# mano_rev_1_1.net
KiCad netlist of a schematic drawn in EAGLE
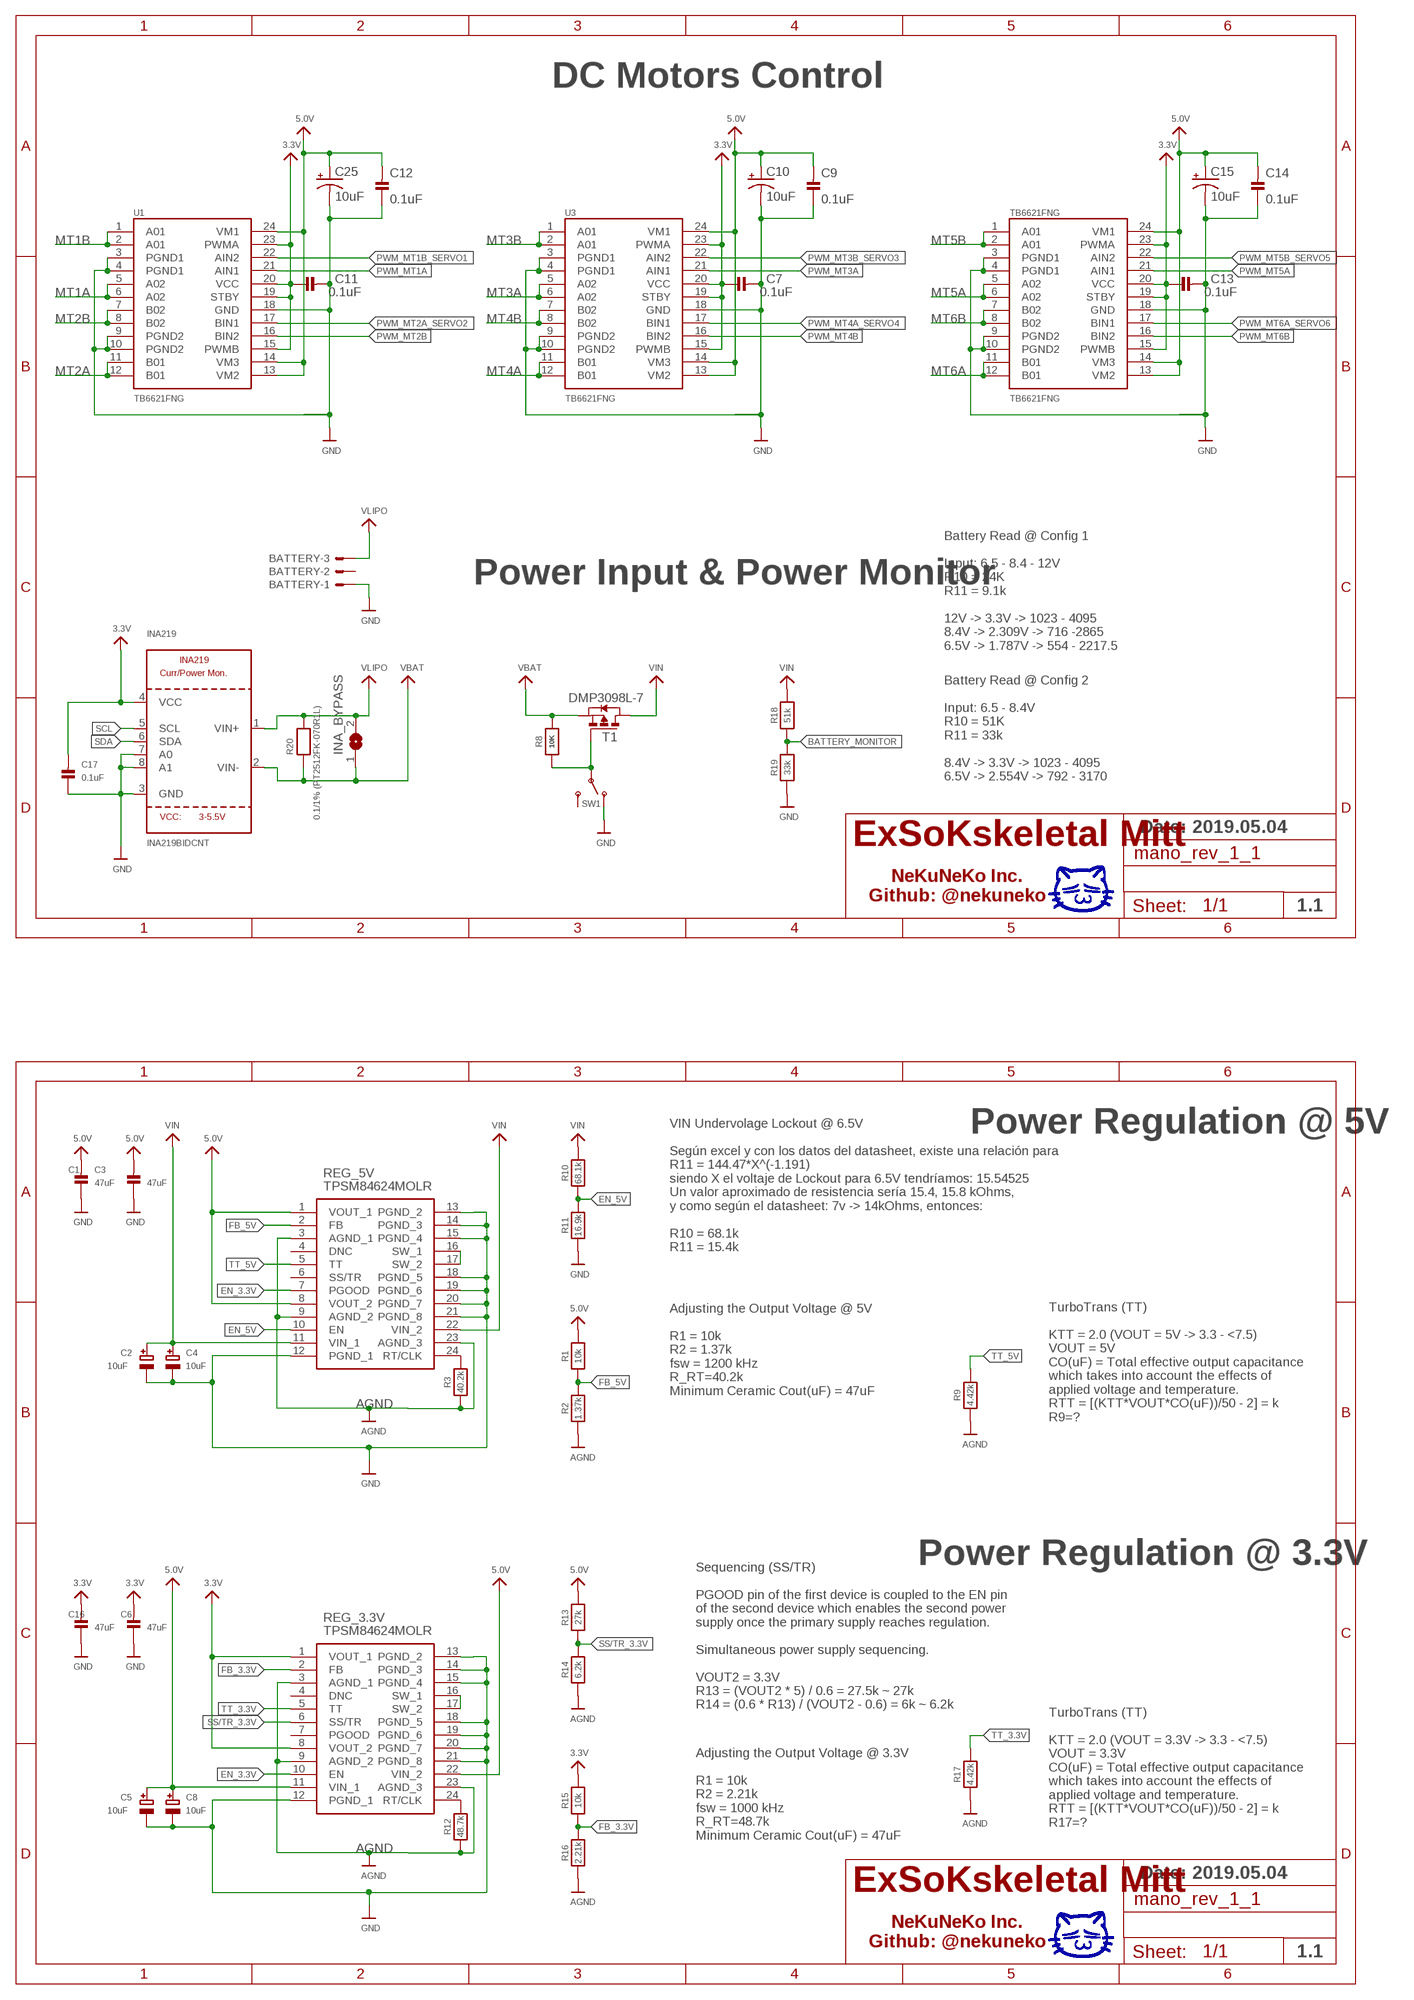
[diagram p0: schematic, sheet 1, part 1 of 2]
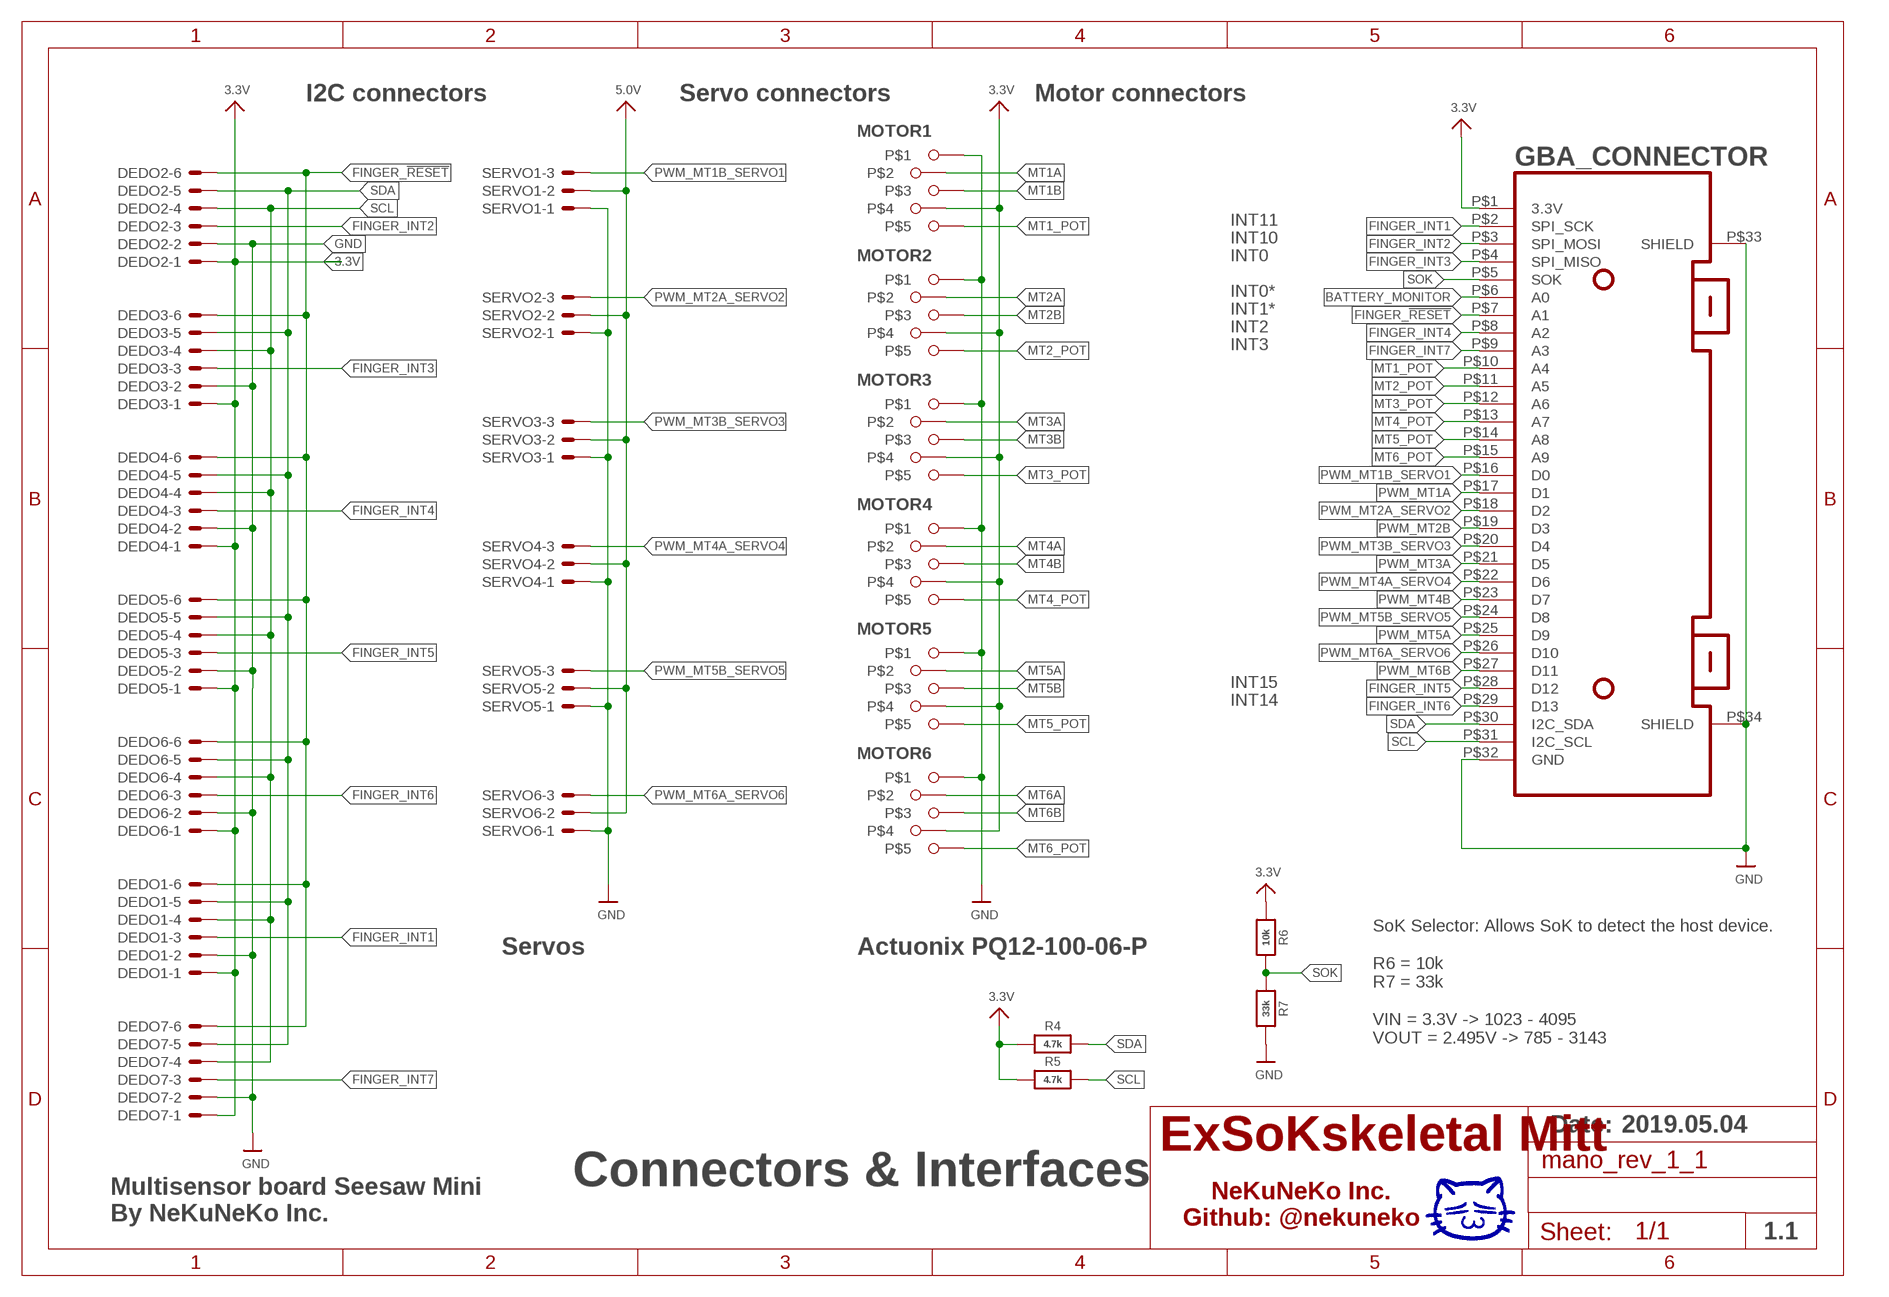
[diagram p1: schematic, sheet 1, part 2 of 2]

(export (version "E")
  (design (tool "Eeschema 10.0.6"))
  (components
    (comp (ref "BATTERY")
      (value "JST-XH-03-PIN-LONG-PAD")
      (footprint "eagle-import:JST-XH-03-PACKAGE-LONG-PAD")
      (libsource (lib "eagle-import") (part "JST-XH-03-PIN-LONG-PAD"))
    )
    (comp (ref "C1")
      (value "47uF")
      (footprint "eagle-import:_0603")
      (libsource (lib "eagle-import") (part "CAP_CERAMIC_0603"))
    )
    (comp (ref "C2")
      (value "10uF")
      (footprint "eagle-import:EIA3216-18_A-R")
      (libsource (lib "eagle-import") (part "CAP_TANTALUMA/3216_REFLOW"))
    )
    (comp (ref "C3")
      (value "47uF")
      (footprint "eagle-import:_0603")
      (libsource (lib "eagle-import") (part "CAP_CERAMIC_0603"))
    )
    (comp (ref "C4")
      (value "10uF")
      (footprint "eagle-import:EIA3216-18_A-R")
      (libsource (lib "eagle-import") (part "CAP_TANTALUMA/3216_REFLOW"))
    )
    (comp (ref "C5")
      (value "10uF")
      (footprint "eagle-import:EIA3216-18_A-R")
      (libsource (lib "eagle-import") (part "CAP_TANTALUMA/3216_REFLOW"))
    )
    (comp (ref "C6")
      (value "47uF")
      (footprint "eagle-import:_0603")
      (libsource (lib "eagle-import") (part "CAP_CERAMIC_0603"))
    )
    (comp (ref "C7")
      (value "0.1uF")
      (footprint "eagle-import:_0603")
      (libsource (lib "eagle-import") (part "CAP_CERAMIC_0603"))
    )
    (comp (ref "C8")
      (value "10uF")
      (footprint "eagle-import:EIA3216-18_A-R")
      (libsource (lib "eagle-import") (part "CAP_TANTALUMA/3216_REFLOW"))
    )
    (comp (ref "C9")
      (value "0.1uF")
      (footprint "eagle-import:_0603")
      (libsource (lib "eagle-import") (part "CAP_CERAMIC_0603"))
    )
    (comp (ref "C10")
      (value "10uF")
      (footprint "eagle-import:0603-POLAR")
      (fields (field (name "MPN") "F981A106MMA"))
      (libsource (lib "eagle-import") (part "10UF-POLAR-0603-6.3V-20%(TANT)"))
    )
    (comp (ref "C11")
      (value "0.1uF")
      (footprint "eagle-import:_0603")
      (libsource (lib "eagle-import") (part "CAP_CERAMIC_0603"))
    )
    (comp (ref "C12")
      (value "0.1uF")
      (footprint "eagle-import:_0603")
      (libsource (lib "eagle-import") (part "CAP_CERAMIC_0603"))
    )
    (comp (ref "C13")
      (value "0.1uF")
      (footprint "eagle-import:_0603")
      (libsource (lib "eagle-import") (part "CAP_CERAMIC_0603"))
    )
    (comp (ref "C14")
      (value "0.1uF")
      (footprint "eagle-import:_0603")
      (libsource (lib "eagle-import") (part "CAP_CERAMIC_0603"))
    )
    (comp (ref "C15")
      (value "10uF")
      (footprint "eagle-import:0603-POLAR")
      (fields (field (name "MPN") "F981A106MMA"))
      (libsource (lib "eagle-import") (part "10UF-POLAR-0603-6.3V-20%(TANT)"))
    )
    (comp (ref "C16")
      (value "47uF")
      (footprint "eagle-import:_0603")
      (libsource (lib "eagle-import") (part "CAP_CERAMIC_0603"))
    )
    (comp (ref "C17")
      (value "0.1uF")
      (footprint "eagle-import:_0603")
      (libsource (lib "eagle-import") (part "CAP_CERAMIC_0603"))
    )
    (comp (ref "C25")
      (value "10uF")
      (footprint "eagle-import:0603-POLAR")
      (fields (field (name "MPN") "F981A106MMA"))
      (libsource (lib "eagle-import") (part "10UF-POLAR-0603-6.3V-20%(TANT)"))
    )
    (comp (ref "DEDO1")
      (value "FINGER_1")
      (footprint "eagle-import:BM06B-SRSS-TB")
      (libsource (lib "eagle-import") (part "?M06B-SRSS-TBB"))
    )
    (comp (ref "DEDO2")
      (value "FINGER_2")
      (footprint "eagle-import:BM06B-SRSS-TB")
      (libsource (lib "eagle-import") (part "?M06B-SRSS-TBB"))
    )
    (comp (ref "DEDO3")
      (value "FINGER_3")
      (footprint "eagle-import:BM06B-SRSS-TB")
      (libsource (lib "eagle-import") (part "?M06B-SRSS-TBB"))
    )
    (comp (ref "DEDO4")
      (value "FINGER_4")
      (footprint "eagle-import:BM06B-SRSS-TB")
      (libsource (lib "eagle-import") (part "?M06B-SRSS-TBB"))
    )
    (comp (ref "DEDO5")
      (value "FINGER_5")
      (footprint "eagle-import:BM06B-SRSS-TB")
      (libsource (lib "eagle-import") (part "?M06B-SRSS-TBB"))
    )
    (comp (ref "DEDO6")
      (value "FINGER_6")
      (footprint "eagle-import:BM06B-SRSS-TB")
      (libsource (lib "eagle-import") (part "?M06B-SRSS-TBB"))
    )
    (comp (ref "DEDO7")
      (value "FINGER_7")
      (footprint "eagle-import:BM06B-SRSS-TB")
      (libsource (lib "eagle-import") (part "?M06B-SRSS-TBB"))
    )
    (comp (ref "GBA_CONNECTOR")
      (value "GBA_CARTRIDGE")
      (footprint "eagle-import:GBA_CARTRIDGE")
      (libsource (lib "eagle-import") (part "GBA_CARTRIDGE"))
    )
    (comp (ref "INA219")
      (value "INA219BIDCNT")
      (footprint "eagle-import:SOT23-8")
      (libsource (lib "eagle-import") (part "INA219"))
    )
    (comp (ref "INA_BYPASS")
      (value "SOLDERJUMPERREFLOW_NOPASTE")
      (footprint "eagle-import:SOLDERJUMPER_REFLOW_NOPASTE")
      (libsource (lib "eagle-import") (part "SOLDERJUMPERREFLOW_NOPASTE"))
    )
    (comp (ref "MOTOR1")
      (value "Actuonix PQ12-100-06-P")
      (footprint "eagle-import:5PIN")
      (libsource (lib "eagle-import") (part "5PIN"))
    )
    (comp (ref "MOTOR2")
      (value "Actuonix PQ12-100-06-P")
      (footprint "eagle-import:5PIN")
      (libsource (lib "eagle-import") (part "5PIN"))
    )
    (comp (ref "MOTOR3")
      (value "Actuonix PQ12-100-06-P")
      (footprint "eagle-import:5PIN")
      (libsource (lib "eagle-import") (part "5PIN"))
    )
    (comp (ref "MOTOR4")
      (value "Actuonix PQ12-100-06-P")
      (footprint "eagle-import:5PIN")
      (libsource (lib "eagle-import") (part "5PIN"))
    )
    (comp (ref "MOTOR5")
      (value "Actuonix PQ12-100-06-P")
      (footprint "eagle-import:5PIN")
      (libsource (lib "eagle-import") (part "5PIN"))
    )
    (comp (ref "MOTOR6")
      (value "Actuonix PQ12-100-06-P")
      (footprint "eagle-import:5PIN")
      (libsource (lib "eagle-import") (part "5PIN"))
    )
    (comp (ref "R1")
      (value "10k")
      (footprint "eagle-import:_0603")
      (libsource (lib "eagle-import") (part "RESISTOR_0603"))
    )
    (comp (ref "R2")
      (value "1.37k")
      (footprint "eagle-import:_0603")
      (libsource (lib "eagle-import") (part "RESISTOR_0603"))
    )
    (comp (ref "R3")
      (value "40.2k")
      (footprint "eagle-import:_0603")
      (libsource (lib "eagle-import") (part "RESISTOR_0603"))
    )
    (comp (ref "R4")
      (value "4.7k")
      (footprint "eagle-import:_0603")
      (libsource (lib "eagle-import") (part "RESISTOR_0603"))
    )
    (comp (ref "R5")
      (value "4.7k")
      (footprint "eagle-import:_0603")
      (libsource (lib "eagle-import") (part "RESISTOR_0603"))
    )
    (comp (ref "R6")
      (value "10k")
      (footprint "eagle-import:_0603")
      (libsource (lib "eagle-import") (part "RESISTOR_0603"))
    )
    (comp (ref "R7")
      (value "33k")
      (footprint "eagle-import:_0603")
      (libsource (lib "eagle-import") (part "RESISTOR_0603"))
    )
    (comp (ref "R8")
      (value "10K")
      (footprint "eagle-import:_0805")
      (libsource (lib "eagle-import") (part "RESISTOR_0805"))
    )
    (comp (ref "R9")
      (value "4.42k")
      (footprint "eagle-import:_0603")
      (libsource (lib "eagle-import") (part "RESISTOR_0603"))
    )
    (comp (ref "R10")
      (value "68.1k")
      (footprint "eagle-import:_0603")
      (libsource (lib "eagle-import") (part "RESISTOR_0603"))
    )
    (comp (ref "R11")
      (value "16.9k")
      (footprint "eagle-import:_0603")
      (libsource (lib "eagle-import") (part "RESISTOR_0603"))
    )
    (comp (ref "R12")
      (value "48.7k")
      (footprint "eagle-import:_0603")
      (libsource (lib "eagle-import") (part "RESISTOR_0603"))
    )
    (comp (ref "R13")
      (value "27k")
      (footprint "eagle-import:_0603")
      (libsource (lib "eagle-import") (part "RESISTOR_0603"))
    )
    (comp (ref "R14")
      (value "6.2k")
      (footprint "eagle-import:_0603")
      (libsource (lib "eagle-import") (part "RESISTOR_0603"))
    )
    (comp (ref "R15")
      (value "10k")
      (footprint "eagle-import:_0603")
      (libsource (lib "eagle-import") (part "RESISTOR_0603"))
    )
    (comp (ref "R16")
      (value "2.21k")
      (footprint "eagle-import:_0603")
      (libsource (lib "eagle-import") (part "RESISTOR_0603"))
    )
    (comp (ref "R17")
      (value "4.42k")
      (footprint "eagle-import:_0603")
      (libsource (lib "eagle-import") (part "RESISTOR_0603"))
    )
    (comp (ref "R18")
      (value "51k")
      (footprint "eagle-import:_0603")
      (libsource (lib "eagle-import") (part "RESISTOR_0603"))
    )
    (comp (ref "R19")
      (value "33k")
      (footprint "eagle-import:_0603")
      (libsource (lib "eagle-import") (part "RESISTOR_0603"))
    )
    (comp (ref "R20")
      (value "0.1/1% (PT2512FK-070R1L)")
      (footprint "eagle-import:2512")
      (libsource (lib "eagle-import") (part "RESISTOR2512"))
    )
    (comp (ref "REG_3.3V")
      (value "TPSM84624MOLR")
      (footprint "eagle-import:TPSM84624MOLR")
      (fields (field (name "MOUSER_PART_NUMBER") "595-TPSM84624MOLR"))
      (libsource (lib "eagle-import") (part "TPSM84624MOLR"))
    )
    (comp (ref "REG_5V")
      (value "TPSM84624MOLR")
      (footprint "eagle-import:TPSM84624MOLR")
      (fields (field (name "MOUSER_PART_NUMBER") "595-TPSM84624MOLR"))
      (libsource (lib "eagle-import") (part "TPSM84624MOLR"))
    )
    (comp (ref "SERVO1")
      (value "JST-XH-03-PIN-LONG-PAD")
      (footprint "eagle-import:JST-XH-03-PACKAGE-LONG-PAD")
      (libsource (lib "eagle-import") (part "JST-XH-03-PIN-LONG-PAD"))
    )
    (comp (ref "SERVO2")
      (value "JST-XH-03-PIN-LONG-PAD")
      (footprint "eagle-import:JST-XH-03-PACKAGE-LONG-PAD")
      (libsource (lib "eagle-import") (part "JST-XH-03-PIN-LONG-PAD"))
    )
    (comp (ref "SERVO3")
      (value "JST-XH-03-PIN-LONG-PAD")
      (footprint "eagle-import:JST-XH-03-PACKAGE-LONG-PAD")
      (libsource (lib "eagle-import") (part "JST-XH-03-PIN-LONG-PAD"))
    )
    (comp (ref "SERVO4")
      (value "JST-XH-03-PIN-LONG-PAD")
      (footprint "eagle-import:JST-XH-03-PACKAGE-LONG-PAD")
      (libsource (lib "eagle-import") (part "JST-XH-03-PIN-LONG-PAD"))
    )
    (comp (ref "SERVO5")
      (value "JST-XH-03-PIN-LONG-PAD")
      (footprint "eagle-import:JST-XH-03-PACKAGE-LONG-PAD")
      (libsource (lib "eagle-import") (part "JST-XH-03-PIN-LONG-PAD"))
    )
    (comp (ref "SERVO6")
      (value "JST-XH-03-PIN-LONG-PAD")
      (footprint "eagle-import:JST-XH-03-PACKAGE-LONG-PAD")
      (libsource (lib "eagle-import") (part "JST-XH-03-PIN-LONG-PAD"))
    )
    (comp (ref "SW1")
      (value "SWITCH_SPDT")
      (footprint "eagle-import:SPDT_SMT_SSSS811101")
      (libsource (lib "eagle-import") (part "SWITCH_SPDT"))
    )
    (comp (ref "T1")
      (value "DMP3098L-7")
      (footprint "eagle-import:SOT-23")
      (libsource (lib "eagle-import") (part "PMOSSOT23"))
    )
    (comp (ref "TB6621FNG")
      (value "TB6621FNG")
      (footprint "eagle-import:SSOP24")
      (libsource (lib "eagle-import") (part "TB6621FNG"))
    )
    (comp (ref "U1")
      (value "TB6621FNG")
      (footprint "eagle-import:SSOP24")
      (libsource (lib "eagle-import") (part "TB6621FNG"))
    )
    (comp (ref "U3")
      (value "TB6621FNG")
      (footprint "eagle-import:SSOP24")
      (libsource (lib "eagle-import") (part "TB6621FNG"))
    )
  )
  (nets
    (net (code "1") (name "/FINGER_~{RESET}") (class "Default")
      (node (ref "DEDO1") (pin "6") (pinfunction "S_6") (pintype "passive"))
      (node (ref "DEDO2") (pin "6") (pinfunction "S_6") (pintype "passive"))
      (node (ref "DEDO3") (pin "6") (pinfunction "S_6") (pintype "passive"))
      (node (ref "DEDO4") (pin "6") (pinfunction "S_6") (pintype "passive"))
      (node (ref "DEDO5") (pin "6") (pinfunction "S_6") (pintype "passive"))
      (node (ref "DEDO6") (pin "6") (pinfunction "S_6") (pintype "passive"))
      (node (ref "DEDO7") (pin "6") (pinfunction "S_6") (pintype "passive"))
      (node (ref "GBA_CONNECTOR") (pin "P$7") (pinfunction "A1_P$7") (pintype "bidirectional"))
    )
    (net (code "2") (name "3.3V") (class "Default")
      (node (ref "C11") (pin "1") (pinfunction "P$1_1") (pintype "passive"))
      (node (ref "C13") (pin "1") (pinfunction "P$1_1") (pintype "passive"))
      (node (ref "C16") (pin "2") (pinfunction "P$2_2") (pintype "passive"))
      (node (ref "C17") (pin "2") (pinfunction "P$2_2") (pintype "passive"))
      (node (ref "C6") (pin "2") (pinfunction "P$2_2") (pintype "passive"))
      (node (ref "C7") (pin "1") (pinfunction "P$1_1") (pintype "passive"))
      (node (ref "DEDO1") (pin "1") (pinfunction "S_1") (pintype "passive"))
      (node (ref "DEDO2") (pin "1") (pinfunction "S_1") (pintype "passive"))
      (node (ref "DEDO3") (pin "1") (pinfunction "S_1") (pintype "passive"))
      (node (ref "DEDO4") (pin "1") (pinfunction "S_1") (pintype "passive"))
      (node (ref "DEDO5") (pin "1") (pinfunction "S_1") (pintype "passive"))
      (node (ref "DEDO6") (pin "1") (pinfunction "S_1") (pintype "passive"))
      (node (ref "DEDO7") (pin "1") (pinfunction "S_1") (pintype "passive"))
      (node (ref "GBA_CONNECTOR") (pin "P$1") (pinfunction "3.3V_P$1") (pintype "power_in"))
      (node (ref "INA219") (pin "4") (pinfunction "VCC_4") (pintype "bidirectional"))
      (node (ref "MOTOR1") (pin "4") (pinfunction "P$4_4") (pintype "bidirectional"))
      (node (ref "MOTOR2") (pin "4") (pinfunction "P$4_4") (pintype "bidirectional"))
      (node (ref "MOTOR3") (pin "4") (pinfunction "P$4_4") (pintype "bidirectional"))
      (node (ref "MOTOR4") (pin "4") (pinfunction "P$4_4") (pintype "bidirectional"))
      (node (ref "MOTOR5") (pin "4") (pinfunction "P$4_4") (pintype "bidirectional"))
      (node (ref "MOTOR6") (pin "4") (pinfunction "P$4_4") (pintype "bidirectional"))
      (node (ref "R15") (pin "2") (pinfunction "2_2") (pintype "passive"))
      (node (ref "R4") (pin "1") (pinfunction "1_1") (pintype "passive"))
      (node (ref "R5") (pin "1") (pinfunction "1_1") (pintype "passive"))
      (node (ref "R6") (pin "1") (pinfunction "1_1") (pintype "passive"))
      (node (ref "REG_3.3V") (pin "1") (pinfunction "VOUT_1_1") (pintype "bidirectional"))
      (node (ref "REG_3.3V") (pin "8") (pinfunction "VOUT_2_8") (pintype "bidirectional"))
      (node (ref "TB6621FNG") (pin "15") (pinfunction "PWMB_15") (pintype "bidirectional"))
      (node (ref "TB6621FNG") (pin "19") (pinfunction "STBY_19") (pintype "bidirectional"))
      (node (ref "TB6621FNG") (pin "20") (pinfunction "VCC_20") (pintype "bidirectional"))
      (node (ref "TB6621FNG") (pin "23") (pinfunction "PWMA_23") (pintype "bidirectional"))
      (node (ref "U1") (pin "15") (pinfunction "PWMB_15") (pintype "bidirectional"))
      (node (ref "U1") (pin "19") (pinfunction "STBY_19") (pintype "bidirectional"))
      (node (ref "U1") (pin "20") (pinfunction "VCC_20") (pintype "bidirectional"))
      (node (ref "U1") (pin "23") (pinfunction "PWMA_23") (pintype "bidirectional"))
      (node (ref "U3") (pin "15") (pinfunction "PWMB_15") (pintype "bidirectional"))
      (node (ref "U3") (pin "19") (pinfunction "STBY_19") (pintype "bidirectional"))
      (node (ref "U3") (pin "20") (pinfunction "VCC_20") (pintype "bidirectional"))
      (node (ref "U3") (pin "23") (pinfunction "PWMA_23") (pintype "bidirectional"))
    )
    (net (code "3") (name "5.0V") (class "Default")
      (node (ref "C1") (pin "2") (pinfunction "P$2_2") (pintype "passive"))
      (node (ref "C10") (pin "+") (pinfunction "+_+") (pintype "passive"))
      (node (ref "C12") (pin "2") (pinfunction "P$2_2") (pintype "passive"))
      (node (ref "C14") (pin "2") (pinfunction "P$2_2") (pintype "passive"))
      (node (ref "C15") (pin "+") (pinfunction "+_+") (pintype "passive"))
      (node (ref "C25") (pin "+") (pinfunction "+_+") (pintype "passive"))
      (node (ref "C3") (pin "2") (pinfunction "P$2_2") (pintype "passive"))
      (node (ref "C5") (pin "+") (pinfunction "+_+") (pintype "passive"))
      (node (ref "C8") (pin "+") (pinfunction "+_+") (pintype "passive"))
      (node (ref "C9") (pin "2") (pinfunction "P$2_2") (pintype "passive"))
      (node (ref "R1") (pin "2") (pinfunction "2_2") (pintype "passive"))
      (node (ref "R13") (pin "2") (pinfunction "2_2") (pintype "passive"))
      (node (ref "REG_3.3V") (pin "11") (pinfunction "VIN_1_11") (pintype "bidirectional"))
      (node (ref "REG_3.3V") (pin "22") (pinfunction "VIN_2_22") (pintype "bidirectional"))
      (node (ref "REG_5V") (pin "1") (pinfunction "VOUT_1_1") (pintype "bidirectional"))
      (node (ref "REG_5V") (pin "8") (pinfunction "VOUT_2_8") (pintype "bidirectional"))
      (node (ref "SERVO1") (pin "2") (pinfunction "S_2") (pintype "passive"))
      (node (ref "SERVO2") (pin "2") (pinfunction "S_2") (pintype "passive"))
      (node (ref "SERVO3") (pin "2") (pinfunction "S_2") (pintype "passive"))
      (node (ref "SERVO4") (pin "2") (pinfunction "S_2") (pintype "passive"))
      (node (ref "SERVO5") (pin "2") (pinfunction "S_2") (pintype "passive"))
      (node (ref "SERVO6") (pin "2") (pinfunction "S_2") (pintype "passive"))
      (node (ref "TB6621FNG") (pin "13") (pinfunction "VM2_13") (pintype "bidirectional"))
      (node (ref "TB6621FNG") (pin "14") (pinfunction "VM3_14") (pintype "bidirectional"))
      (node (ref "TB6621FNG") (pin "24") (pinfunction "VM1_24") (pintype "bidirectional"))
      (node (ref "U1") (pin "13") (pinfunction "VM2_13") (pintype "bidirectional"))
      (node (ref "U1") (pin "14") (pinfunction "VM3_14") (pintype "bidirectional"))
      (node (ref "U1") (pin "24") (pinfunction "VM1_24") (pintype "bidirectional"))
      (node (ref "U3") (pin "13") (pinfunction "VM2_13") (pintype "bidirectional"))
      (node (ref "U3") (pin "14") (pinfunction "VM3_14") (pintype "bidirectional"))
      (node (ref "U3") (pin "24") (pinfunction "VM1_24") (pintype "bidirectional"))
    )
    (net (code "4") (name "AGND") (class "Default")
      (node (ref "R12") (pin "1") (pinfunction "1_1") (pintype "passive"))
      (node (ref "R14") (pin "1") (pinfunction "1_1") (pintype "passive"))
      (node (ref "R16") (pin "1") (pinfunction "1_1") (pintype "passive"))
      (node (ref "R17") (pin "1") (pinfunction "1_1") (pintype "passive"))
      (node (ref "R2") (pin "1") (pinfunction "1_1") (pintype "passive"))
      (node (ref "R3") (pin "1") (pinfunction "1_1") (pintype "passive"))
      (node (ref "R9") (pin "1") (pinfunction "1_1") (pintype "passive"))
      (node (ref "REG_3.3V") (pin "23") (pinfunction "AGND_3_23") (pintype "bidirectional"))
      (node (ref "REG_3.3V") (pin "3") (pinfunction "AGND_1_3") (pintype "bidirectional"))
      (node (ref "REG_3.3V") (pin "9") (pinfunction "AGND_2_9") (pintype "bidirectional"))
      (node (ref "REG_5V") (pin "23") (pinfunction "AGND_3_23") (pintype "bidirectional"))
      (node (ref "REG_5V") (pin "3") (pinfunction "AGND_1_3") (pintype "bidirectional"))
      (node (ref "REG_5V") (pin "9") (pinfunction "AGND_2_9") (pintype "bidirectional"))
    )
    (net (code "5") (name "BATTERY_MONITOR") (class "Default")
      (node (ref "GBA_CONNECTOR") (pin "P$6") (pinfunction "A0_P$6") (pintype "bidirectional"))
      (node (ref "R18") (pin "1") (pinfunction "1_1") (pintype "passive"))
      (node (ref "R19") (pin "2") (pinfunction "2_2") (pintype "passive"))
    )
    (net (code "6") (name "EN_3.3V") (class "Default")
      (node (ref "REG_3.3V") (pin "10") (pinfunction "EN_10") (pintype "bidirectional"))
      (node (ref "REG_5V") (pin "7") (pinfunction "PGOOD_7") (pintype "bidirectional"))
    )
    (net (code "7") (name "EN_5V") (class "Default")
      (node (ref "R10") (pin "1") (pinfunction "1_1") (pintype "passive"))
      (node (ref "R11") (pin "2") (pinfunction "2_2") (pintype "passive"))
      (node (ref "REG_5V") (pin "10") (pinfunction "EN_10") (pintype "bidirectional"))
    )
    (net (code "8") (name "FB_3.3V") (class "Default")
      (node (ref "R15") (pin "1") (pinfunction "1_1") (pintype "passive"))
      (node (ref "R16") (pin "2") (pinfunction "2_2") (pintype "passive"))
      (node (ref "REG_3.3V") (pin "2") (pinfunction "FB_2") (pintype "bidirectional"))
    )
    (net (code "9") (name "FB_5V") (class "Default")
      (node (ref "R1") (pin "1") (pinfunction "1_1") (pintype "passive"))
      (node (ref "R2") (pin "2") (pinfunction "2_2") (pintype "passive"))
      (node (ref "REG_5V") (pin "2") (pinfunction "FB_2") (pintype "bidirectional"))
    )
    (net (code "10") (name "FINGER_INT1") (class "Default")
      (node (ref "DEDO1") (pin "3") (pinfunction "S_3") (pintype "passive"))
      (node (ref "GBA_CONNECTOR") (pin "P$2") (pinfunction "SPI_SCK_P$2") (pintype "bidirectional"))
    )
    (net (code "11") (name "FINGER_INT2") (class "Default")
      (node (ref "DEDO2") (pin "3") (pinfunction "S_3") (pintype "passive"))
      (node (ref "GBA_CONNECTOR") (pin "P$3") (pinfunction "SPI_MOSI_P$3") (pintype "bidirectional"))
    )
    (net (code "12") (name "FINGER_INT3") (class "Default")
      (node (ref "DEDO3") (pin "3") (pinfunction "S_3") (pintype "passive"))
      (node (ref "GBA_CONNECTOR") (pin "P$4") (pinfunction "SPI_MISO_P$4") (pintype "bidirectional"))
    )
    (net (code "13") (name "FINGER_INT4") (class "Default")
      (node (ref "DEDO4") (pin "3") (pinfunction "S_3") (pintype "passive"))
      (node (ref "GBA_CONNECTOR") (pin "P$8") (pinfunction "A2_P$8") (pintype "bidirectional"))
    )
    (net (code "14") (name "FINGER_INT5") (class "Default")
      (node (ref "DEDO5") (pin "3") (pinfunction "S_3") (pintype "passive"))
      (node (ref "GBA_CONNECTOR") (pin "P$28") (pinfunction "D12_P$28") (pintype "bidirectional"))
    )
    (net (code "15") (name "FINGER_INT6") (class "Default")
      (node (ref "DEDO6") (pin "3") (pinfunction "S_3") (pintype "passive"))
      (node (ref "GBA_CONNECTOR") (pin "P$29") (pinfunction "D13_P$29") (pintype "bidirectional"))
    )
    (net (code "16") (name "FINGER_INT7") (class "Default")
      (node (ref "DEDO7") (pin "3") (pinfunction "S_3") (pintype "passive"))
      (node (ref "GBA_CONNECTOR") (pin "P$9") (pinfunction "A3_P$9") (pintype "bidirectional"))
    )
    (net (code "17") (name "GND") (class "Default")
      (node (ref "BATTERY") (pin "1") (pinfunction "S_1") (pintype "passive"))
      (node (ref "C1") (pin "1") (pinfunction "P$1_1") (pintype "passive"))
      (node (ref "C10") (pin "-") (pinfunction "-_-") (pintype "passive"))
      (node (ref "C11") (pin "2") (pinfunction "P$2_2") (pintype "passive"))
      (node (ref "C12") (pin "1") (pinfunction "P$1_1") (pintype "passive"))
      (node (ref "C13") (pin "2") (pinfunction "P$2_2") (pintype "passive"))
      (node (ref "C14") (pin "1") (pinfunction "P$1_1") (pintype "passive"))
      (node (ref "C15") (pin "-") (pinfunction "-_-") (pintype "passive"))
      (node (ref "C16") (pin "1") (pinfunction "P$1_1") (pintype "passive"))
      (node (ref "C17") (pin "1") (pinfunction "P$1_1") (pintype "passive"))
      (node (ref "C2") (pin "-") (pinfunction "-_-") (pintype "passive"))
      (node (ref "C25") (pin "-") (pinfunction "-_-") (pintype "passive"))
      (node (ref "C3") (pin "1") (pinfunction "P$1_1") (pintype "passive"))
      (node (ref "C4") (pin "-") (pinfunction "-_-") (pintype "passive"))
      (node (ref "C5") (pin "-") (pinfunction "-_-") (pintype "passive"))
      (node (ref "C6") (pin "1") (pinfunction "P$1_1") (pintype "passive"))
      (node (ref "C7") (pin "2") (pinfunction "P$2_2") (pintype "passive"))
      (node (ref "C8") (pin "-") (pinfunction "-_-") (pintype "passive"))
      (node (ref "C9") (pin "1") (pinfunction "P$1_1") (pintype "passive"))
      (node (ref "DEDO1") (pin "2") (pinfunction "S_2") (pintype "passive"))
      (node (ref "DEDO2") (pin "2") (pinfunction "S_2") (pintype "passive"))
      (node (ref "DEDO3") (pin "2") (pinfunction "S_2") (pintype "passive"))
      (node (ref "DEDO4") (pin "2") (pinfunction "S_2") (pintype "passive"))
      (node (ref "DEDO5") (pin "2") (pinfunction "S_2") (pintype "passive"))
      (node (ref "DEDO6") (pin "2") (pinfunction "S_2") (pintype "passive"))
      (node (ref "DEDO7") (pin "2") (pinfunction "S_2") (pintype "passive"))
      (node (ref "GBA_CONNECTOR") (pin "P$32") (pinfunction "GND_P$32") (pintype "power_in"))
      (node (ref "GBA_CONNECTOR") (pin "P$33") (pinfunction "SHIELD_P$33") (pintype "bidirectional"))
      (node (ref "GBA_CONNECTOR") (pin "P$34") (pinfunction "SHIELD_P$34") (pintype "bidirectional"))
      (node (ref "INA219") (pin "3") (pinfunction "GND_3") (pintype "bidirectional"))
      (node (ref "INA219") (pin "7") (pinfunction "A0_7") (pintype "bidirectional"))
      (node (ref "INA219") (pin "8") (pinfunction "A1_8") (pintype "bidirectional"))
      (node (ref "MOTOR1") (pin "1") (pinfunction "P$1_1") (pintype "bidirectional"))
      (node (ref "MOTOR2") (pin "1") (pinfunction "P$1_1") (pintype "bidirectional"))
      (node (ref "MOTOR3") (pin "1") (pinfunction "P$1_1") (pintype "bidirectional"))
      (node (ref "MOTOR4") (pin "1") (pinfunction "P$1_1") (pintype "bidirectional"))
      (node (ref "MOTOR5") (pin "1") (pinfunction "P$1_1") (pintype "bidirectional"))
      (node (ref "MOTOR6") (pin "1") (pinfunction "P$1_1") (pintype "bidirectional"))
      (node (ref "R11") (pin "1") (pinfunction "1_1") (pintype "passive"))
      (node (ref "R19") (pin "1") (pinfunction "1_1") (pintype "passive"))
      (node (ref "R7") (pin "2") (pinfunction "2_2") (pintype "passive"))
      (node (ref "REG_3.3V") (pin "12") (pinfunction "PGND_1_12") (pintype "bidirectional"))
      (node (ref "REG_3.3V") (pin "13") (pinfunction "PGND_2_13") (pintype "bidirectional"))
      (node (ref "REG_3.3V") (pin "14") (pinfunction "PGND_3_14") (pintype "bidirectional"))
      (node (ref "REG_3.3V") (pin "15") (pinfunction "PGND_4_15") (pintype "bidirectional"))
      (node (ref "REG_3.3V") (pin "18") (pinfunction "PGND_5_18") (pintype "bidirectional"))
      (node (ref "REG_3.3V") (pin "19") (pinfunction "PGND_6_19") (pintype "bidirectional"))
      (node (ref "REG_3.3V") (pin "20") (pinfunction "PGND_7_20") (pintype "bidirectional"))
      (node (ref "REG_3.3V") (pin "21") (pinfunction "PGND_8_21") (pintype "bidirectional"))
      (node (ref "REG_5V") (pin "12") (pinfunction "PGND_1_12") (pintype "bidirectional"))
      (node (ref "REG_5V") (pin "13") (pinfunction "PGND_2_13") (pintype "bidirectional"))
      (node (ref "REG_5V") (pin "14") (pinfunction "PGND_3_14") (pintype "bidirectional"))
      (node (ref "REG_5V") (pin "15") (pinfunction "PGND_4_15") (pintype "bidirectional"))
      (node (ref "REG_5V") (pin "18") (pinfunction "PGND_5_18") (pintype "bidirectional"))
      (node (ref "REG_5V") (pin "19") (pinfunction "PGND_6_19") (pintype "bidirectional"))
      (node (ref "REG_5V") (pin "20") (pinfunction "PGND_7_20") (pintype "bidirectional"))
      (node (ref "REG_5V") (pin "21") (pinfunction "PGND_8_21") (pintype "bidirectional"))
      (node (ref "SERVO1") (pin "1") (pinfunction "S_1") (pintype "passive"))
      (node (ref "SERVO2") (pin "1") (pinfunction "S_1") (pintype "passive"))
      (node (ref "SERVO3") (pin "1") (pinfunction "S_1") (pintype "passive"))
      (node (ref "SERVO4") (pin "1") (pinfunction "S_1") (pintype "passive"))
      (node (ref "SERVO5") (pin "1") (pinfunction "S_1") (pintype "passive"))
      (node (ref "SERVO6") (pin "1") (pinfunction "S_1") (pintype "passive"))
      (node (ref "SW1") (pin "A") (pinfunction "O_A") (pintype "passive"))
      (node (ref "TB6621FNG") (pin "10") (pinfunction "PGND2_10") (pintype "bidirectional"))
      (node (ref "TB6621FNG") (pin "18") (pinfunction "GND_18") (pintype "bidirectional"))
      (node (ref "TB6621FNG") (pin "3") (pinfunction "PGND1_3") (pintype "bidirectional"))
      (node (ref "TB6621FNG") (pin "4") (pinfunction "PGND1_4") (pintype "bidirectional"))
      (node (ref "TB6621FNG") (pin "9") (pinfunction "PGND2_9") (pintype "bidirectional"))
      (node (ref "U1") (pin "10") (pinfunction "PGND2_10") (pintype "bidirectional"))
      (node (ref "U1") (pin "18") (pinfunction "GND_18") (pintype "bidirectional"))
      (node (ref "U1") (pin "3") (pinfunction "PGND1_3") (pintype "bidirectional"))
      (node (ref "U1") (pin "4") (pinfunction "PGND1_4") (pintype "bidirectional"))
      (node (ref "U1") (pin "9") (pinfunction "PGND2_9") (pintype "bidirectional"))
      (node (ref "U3") (pin "10") (pinfunction "PGND2_10") (pintype "bidirectional"))
      (node (ref "U3") (pin "18") (pinfunction "GND_18") (pintype "bidirectional"))
      (node (ref "U3") (pin "3") (pinfunction "PGND1_3") (pintype "bidirectional"))
      (node (ref "U3") (pin "4") (pinfunction "PGND1_4") (pintype "bidirectional"))
      (node (ref "U3") (pin "9") (pinfunction "PGND2_9") (pintype "bidirectional"))
    )
    (net (code "18") (name "MT1A") (class "Default")
      (node (ref "MOTOR1") (pin "2") (pinfunction "P$2_2") (pintype "bidirectional"))
      (node (ref "U1") (pin "5") (pinfunction "A02_5") (pintype "bidirectional"))
      (node (ref "U1") (pin "6") (pinfunction "A02_6") (pintype "bidirectional"))
    )
    (net (code "19") (name "MT1B") (class "Default")
      (node (ref "MOTOR1") (pin "3") (pinfunction "P$3_3") (pintype "bidirectional"))
      (node (ref "U1") (pin "1") (pinfunction "A01_1") (pintype "bidirectional"))
      (node (ref "U1") (pin "2") (pinfunction "A01_2") (pintype "bidirectional"))
    )
    (net (code "20") (name "MT1_POT") (class "Default")
      (node (ref "GBA_CONNECTOR") (pin "P$10") (pinfunction "A4_P$10") (pintype "bidirectional"))
      (node (ref "MOTOR1") (pin "5") (pinfunction "P$5_5") (pintype "bidirectional"))
    )
    (net (code "21") (name "MT2A") (class "Default")
      (node (ref "MOTOR2") (pin "2") (pinfunction "P$2_2") (pintype "bidirectional"))
      (node (ref "U1") (pin "11") (pinfunction "B01_11") (pintype "bidirectional"))
      (node (ref "U1") (pin "12") (pinfunction "B01_12") (pintype "bidirectional"))
    )
    (net (code "22") (name "MT2B") (class "Default")
      (node (ref "MOTOR2") (pin "3") (pinfunction "P$3_3") (pintype "bidirectional"))
      (node (ref "U1") (pin "7") (pinfunction "B02_7") (pintype "bidirectional"))
      (node (ref "U1") (pin "8") (pinfunction "B02_8") (pintype "bidirectional"))
    )
    (net (code "23") (name "MT2_POT") (class "Default")
      (node (ref "GBA_CONNECTOR") (pin "P$11") (pinfunction "A5_P$11") (pintype "bidirectional"))
      (node (ref "MOTOR2") (pin "5") (pinfunction "P$5_5") (pintype "bidirectional"))
    )
    (net (code "24") (name "MT3A") (class "Default")
      (node (ref "MOTOR3") (pin "2") (pinfunction "P$2_2") (pintype "bidirectional"))
      (node (ref "U3") (pin "5") (pinfunction "A02_5") (pintype "bidirectional"))
      (node (ref "U3") (pin "6") (pinfunction "A02_6") (pintype "bidirectional"))
    )
    (net (code "25") (name "MT3B") (class "Default")
      (node (ref "MOTOR3") (pin "3") (pinfunction "P$3_3") (pintype "bidirectional"))
      (node (ref "U3") (pin "1") (pinfunction "A01_1") (pintype "bidirectional"))
      (node (ref "U3") (pin "2") (pinfunction "A01_2") (pintype "bidirectional"))
    )
    (net (code "26") (name "MT3_POT") (class "Default")
      (node (ref "GBA_CONNECTOR") (pin "P$12") (pinfunction "A6_P$12") (pintype "bidirectional"))
      (node (ref "MOTOR3") (pin "5") (pinfunction "P$5_5") (pintype "bidirectional"))
    )
    (net (code "27") (name "MT4A") (class "Default")
      (node (ref "MOTOR4") (pin "2") (pinfunction "P$2_2") (pintype "bidirectional"))
      (node (ref "U3") (pin "11") (pinfunction "B01_11") (pintype "bidirectional"))
      (node (ref "U3") (pin "12") (pinfunction "B01_12") (pintype "bidirectional"))
    )
    (net (code "28") (name "MT4B") (class "Default")
      (node (ref "MOTOR4") (pin "3") (pinfunction "P$3_3") (pintype "bidirectional"))
      (node (ref "U3") (pin "7") (pinfunction "B02_7") (pintype "bidirectional"))
      (node (ref "U3") (pin "8") (pinfunction "B02_8") (pintype "bidirectional"))
    )
    (net (code "29") (name "MT4_POT") (class "Default")
      (node (ref "GBA_CONNECTOR") (pin "P$13") (pinfunction "A7_P$13") (pintype "bidirectional"))
      (node (ref "MOTOR4") (pin "5") (pinfunction "P$5_5") (pintype "bidirectional"))
    )
    (net (code "30") (name "MT5A") (class "Default")
      (node (ref "MOTOR5") (pin "2") (pinfunction "P$2_2") (pintype "bidirectional"))
      (node (ref "TB6621FNG") (pin "5") (pinfunction "A02_5") (pintype "bidirectional"))
      (node (ref "TB6621FNG") (pin "6") (pinfunction "A02_6") (pintype "bidirectional"))
    )
    (net (code "31") (name "MT5B") (class "Default")
      (node (ref "MOTOR5") (pin "3") (pinfunction "P$3_3") (pintype "bidirectional"))
      (node (ref "TB6621FNG") (pin "1") (pinfunction "A01_1") (pintype "bidirectional"))
      (node (ref "TB6621FNG") (pin "2") (pinfunction "A01_2") (pintype "bidirectional"))
    )
    (net (code "32") (name "MT5_POT") (class "Default")
      (node (ref "GBA_CONNECTOR") (pin "P$14") (pinfunction "A8_P$14") (pintype "bidirectional"))
      (node (ref "MOTOR5") (pin "5") (pinfunction "P$5_5") (pintype "bidirectional"))
    )
    (net (code "33") (name "MT6A") (class "Default")
      (node (ref "MOTOR6") (pin "2") (pinfunction "P$2_2") (pintype "bidirectional"))
      (node (ref "TB6621FNG") (pin "11") (pinfunction "B01_11") (pintype "bidirectional"))
      (node (ref "TB6621FNG") (pin "12") (pinfunction "B01_12") (pintype "bidirectional"))
    )
    (net (code "34") (name "MT6B") (class "Default")
      (node (ref "MOTOR6") (pin "3") (pinfunction "P$3_3") (pintype "bidirectional"))
      (node (ref "TB6621FNG") (pin "7") (pinfunction "B02_7") (pintype "bidirectional"))
      (node (ref "TB6621FNG") (pin "8") (pinfunction "B02_8") (pintype "bidirectional"))
    )
    (net (code "35") (name "MT6_POT") (class "Default")
      (node (ref "GBA_CONNECTOR") (pin "P$15") (pinfunction "A9_P$15") (pintype "bidirectional"))
      (node (ref "MOTOR6") (pin "5") (pinfunction "P$5_5") (pintype "bidirectional"))
    )
    (net (code "36") (name "Net-(REG_3.3V-RT{slash}CLK)") (class "Default")
      (node (ref "R12") (pin "2") (pinfunction "2_2") (pintype "passive"))
      (node (ref "REG_3.3V") (pin "24") (pinfunction "RT/CLK_24") (pintype "bidirectional"))
    )
    (net (code "37") (name "Net-(REG_3.3V-SW_1)") (class "Default")
      (node (ref "REG_3.3V") (pin "16") (pinfunction "SW_1_16") (pintype "bidirectional"))
      (node (ref "REG_3.3V") (pin "17") (pinfunction "SW_2_17") (pintype "bidirectional"))
    )
    (net (code "38") (name "Net-(REG_5V-RT{slash}CLK)") (class "Default")
      (node (ref "R3") (pin "2") (pinfunction "2_2") (pintype "passive"))
      (node (ref "REG_5V") (pin "24") (pinfunction "RT/CLK_24") (pintype "bidirectional"))
    )
    (net (code "39") (name "Net-(REG_5V-SW_1)") (class "Default")
      (node (ref "REG_5V") (pin "16") (pinfunction "SW_1_16") (pintype "bidirectional"))
      (node (ref "REG_5V") (pin "17") (pinfunction "SW_2_17") (pintype "bidirectional"))
    )
    (net (code "40") (name "Net-(SW1-P)") (class "Default")
      (node (ref "R8") (pin "1") (pinfunction "1_1") (pintype "passive"))
      (node (ref "SW1") (pin "B") (pinfunction "P_B") (pintype "passive"))
      (node (ref "T1") (pin "3") (pinfunction "G_3") (pintype "passive"))
    )
    (net (code "41") (name "PWM_MT1A") (class "Default")
      (node (ref "GBA_CONNECTOR") (pin "P$17") (pinfunction "D1_P$17") (pintype "bidirectional"))
      (node (ref "U1") (pin "21") (pinfunction "AIN1_21") (pintype "bidirectional"))
    )
    (net (code "42") (name "PWM_MT1B_SERVO1") (class "Default")
      (node (ref "GBA_CONNECTOR") (pin "P$16") (pinfunction "D0_P$16") (pintype "bidirectional"))
      (node (ref "SERVO1") (pin "3") (pinfunction "S_3") (pintype "passive"))
      (node (ref "U1") (pin "22") (pinfunction "AIN2_22") (pintype "bidirectional"))
    )
    (net (code "43") (name "PWM_MT2A_SERVO2") (class "Default")
      (node (ref "GBA_CONNECTOR") (pin "P$18") (pinfunction "D2_P$18") (pintype "bidirectional"))
      (node (ref "SERVO2") (pin "3") (pinfunction "S_3") (pintype "passive"))
      (node (ref "U1") (pin "17") (pinfunction "BIN1_17") (pintype "bidirectional"))
    )
    (net (code "44") (name "PWM_MT2B") (class "Default")
      (node (ref "GBA_CONNECTOR") (pin "P$19") (pinfunction "D3_P$19") (pintype "bidirectional"))
      (node (ref "U1") (pin "16") (pinfunction "BIN2_16") (pintype "bidirectional"))
    )
    (net (code "45") (name "PWM_MT3A") (class "Default")
      (node (ref "GBA_CONNECTOR") (pin "P$21") (pinfunction "D5_P$21") (pintype "bidirectional"))
      (node (ref "U3") (pin "21") (pinfunction "AIN1_21") (pintype "bidirectional"))
    )
    (net (code "46") (name "PWM_MT3B_SERVO3") (class "Default")
      (node (ref "GBA_CONNECTOR") (pin "P$20") (pinfunction "D4_P$20") (pintype "bidirectional"))
      (node (ref "SERVO3") (pin "3") (pinfunction "S_3") (pintype "passive"))
      (node (ref "U3") (pin "22") (pinfunction "AIN2_22") (pintype "bidirectional"))
    )
    (net (code "47") (name "PWM_MT4A_SERVO4") (class "Default")
      (node (ref "GBA_CONNECTOR") (pin "P$22") (pinfunction "D6_P$22") (pintype "bidirectional"))
      (node (ref "SERVO4") (pin "3") (pinfunction "S_3") (pintype "passive"))
      (node (ref "U3") (pin "17") (pinfunction "BIN1_17") (pintype "bidirectional"))
    )
    (net (code "48") (name "PWM_MT4B") (class "Default")
      (node (ref "GBA_CONNECTOR") (pin "P$23") (pinfunction "D7_P$23") (pintype "bidirectional"))
      (node (ref "U3") (pin "16") (pinfunction "BIN2_16") (pintype "bidirectional"))
    )
    (net (code "49") (name "PWM_MT5A") (class "Default")
      (node (ref "GBA_CONNECTOR") (pin "P$25") (pinfunction "D9_P$25") (pintype "bidirectional"))
      (node (ref "TB6621FNG") (pin "21") (pinfunction "AIN1_21") (pintype "bidirectional"))
    )
    (net (code "50") (name "PWM_MT5B_SERVO5") (class "Default")
      (node (ref "GBA_CONNECTOR") (pin "P$24") (pinfunction "D8_P$24") (pintype "bidirectional"))
      (node (ref "SERVO5") (pin "3") (pinfunction "S_3") (pintype "passive"))
      (node (ref "TB6621FNG") (pin "22") (pinfunction "AIN2_22") (pintype "bidirectional"))
    )
    (net (code "51") (name "PWM_MT6A_SERVO6") (class "Default")
      (node (ref "GBA_CONNECTOR") (pin "P$26") (pinfunction "D10_P$26") (pintype "bidirectional"))
      (node (ref "SERVO6") (pin "3") (pinfunction "S_3") (pintype "passive"))
      (node (ref "TB6621FNG") (pin "17") (pinfunction "BIN1_17") (pintype "bidirectional"))
    )
    (net (code "52") (name "PWM_MT6B") (class "Default")
      (node (ref "GBA_CONNECTOR") (pin "P$27") (pinfunction "D11_P$27") (pintype "bidirectional"))
      (node (ref "TB6621FNG") (pin "16") (pinfunction "BIN2_16") (pintype "bidirectional"))
    )
    (net (code "53") (name "SCL") (class "Default")
      (node (ref "DEDO1") (pin "4") (pinfunction "S_4") (pintype "passive"))
      (node (ref "DEDO2") (pin "4") (pinfunction "S_4") (pintype "passive"))
      (node (ref "DEDO3") (pin "4") (pinfunction "S_4") (pintype "passive"))
      (node (ref "DEDO4") (pin "4") (pinfunction "S_4") (pintype "passive"))
      (node (ref "DEDO5") (pin "4") (pinfunction "S_4") (pintype "passive"))
      (node (ref "DEDO6") (pin "4") (pinfunction "S_4") (pintype "passive"))
      (node (ref "DEDO7") (pin "4") (pinfunction "S_4") (pintype "passive"))
      (node (ref "GBA_CONNECTOR") (pin "P$31") (pinfunction "I2C_SCL_P$31") (pintype "bidirectional"))
      (node (ref "INA219") (pin "5") (pinfunction "SCL_5") (pintype "bidirectional"))
      (node (ref "R5") (pin "2") (pinfunction "2_2") (pintype "passive"))
    )
    (net (code "54") (name "SDA") (class "Default")
      (node (ref "DEDO1") (pin "5") (pinfunction "S_5") (pintype "passive"))
      (node (ref "DEDO2") (pin "5") (pinfunction "S_5") (pintype "passive"))
      (node (ref "DEDO3") (pin "5") (pinfunction "S_5") (pintype "passive"))
      (node (ref "DEDO4") (pin "5") (pinfunction "S_5") (pintype "passive"))
      (node (ref "DEDO5") (pin "5") (pinfunction "S_5") (pintype "passive"))
      (node (ref "DEDO6") (pin "5") (pinfunction "S_5") (pintype "passive"))
      (node (ref "DEDO7") (pin "5") (pinfunction "S_5") (pintype "passive"))
      (node (ref "GBA_CONNECTOR") (pin "P$30") (pinfunction "I2C_SDA_P$30") (pintype "bidirectional"))
      (node (ref "INA219") (pin "6") (pinfunction "SDA_6") (pintype "bidirectional"))
      (node (ref "R4") (pin "2") (pinfunction "2_2") (pintype "passive"))
    )
    (net (code "55") (name "SOK") (class "Default")
      (node (ref "GBA_CONNECTOR") (pin "P$5") (pinfunction "SOK_P$5") (pintype "bidirectional"))
      (node (ref "R6") (pin "2") (pinfunction "2_2") (pintype "passive"))
      (node (ref "R7") (pin "1") (pinfunction "1_1") (pintype "passive"))
    )
    (net (code "56") (name "SS{slash}TR_3.3V") (class "Default")
      (node (ref "R13") (pin "1") (pinfunction "1_1") (pintype "passive"))
      (node (ref "R14") (pin "2") (pinfunction "2_2") (pintype "passive"))
      (node (ref "REG_3.3V") (pin "6") (pinfunction "SS/TR_6") (pintype "bidirectional"))
    )
    (net (code "57") (name "TT_3.3V") (class "Default")
      (node (ref "R17") (pin "2") (pinfunction "2_2") (pintype "passive"))
      (node (ref "REG_3.3V") (pin "5") (pinfunction "TT_5") (pintype "bidirectional"))
    )
    (net (code "58") (name "TT_5V") (class "Default")
      (node (ref "R9") (pin "2") (pinfunction "2_2") (pintype "passive"))
      (node (ref "REG_5V") (pin "5") (pinfunction "TT_5") (pintype "bidirectional"))
    )
    (net (code "59") (name "VBAT") (class "Default")
      (node (ref "INA219") (pin "2") (pinfunction "VIN-_2") (pintype "bidirectional"))
      (node (ref "INA_BYPASS") (pin "1") (pinfunction "1_1") (pintype "passive"))
      (node (ref "R20") (pin "1") (pinfunction "1_1") (pintype "passive"))
      (node (ref "R8") (pin "2") (pinfunction "2_2") (pintype "passive"))
      (node (ref "T1") (pin "2") (pinfunction "S_2") (pintype "passive"))
    )
    (net (code "60") (name "VIN") (class "Default")
      (node (ref "C2") (pin "+") (pinfunction "+_+") (pintype "passive"))
      (node (ref "C4") (pin "+") (pinfunction "+_+") (pintype "passive"))
      (node (ref "R10") (pin "2") (pinfunction "2_2") (pintype "passive"))
      (node (ref "R18") (pin "2") (pinfunction "2_2") (pintype "passive"))
      (node (ref "REG_5V") (pin "11") (pinfunction "VIN_1_11") (pintype "bidirectional"))
      (node (ref "REG_5V") (pin "22") (pinfunction "VIN_2_22") (pintype "bidirectional"))
      (node (ref "T1") (pin "1") (pinfunction "D_1") (pintype "passive"))
    )
    (net (code "61") (name "VLIPO") (class "Default")
      (node (ref "BATTERY") (pin "3") (pinfunction "S_3") (pintype "passive"))
      (node (ref "INA219") (pin "1") (pinfunction "VIN+_1") (pintype "bidirectional"))
      (node (ref "INA_BYPASS") (pin "2") (pinfunction "2_2") (pintype "passive"))
      (node (ref "R20") (pin "2") (pinfunction "2_2") (pintype "passive"))
    )
    (net (code "62") (name "unconnected-(BATTERYB-S-Pad2)") (class "Default")
      (node (ref "BATTERY") (pin "2") (pinfunction "S_2") (pintype "passive"))
    )
    (net (code "63") (name "unconnected-(REG_3.3V-DNC-Pad4)") (class "Default")
      (node (ref "REG_3.3V") (pin "4") (pinfunction "DNC_4") (pintype "bidirectional"))
    )
    (net (code "64") (name "unconnected-(REG_3.3V-PGOOD-Pad7)") (class "Default")
      (node (ref "REG_3.3V") (pin "7") (pinfunction "PGOOD_7") (pintype "bidirectional"))
    )
    (net (code "65") (name "unconnected-(REG_5V-DNC-Pad4)") (class "Default")
      (node (ref "REG_5V") (pin "4") (pinfunction "DNC_4") (pintype "bidirectional"))
    )
    (net (code "66") (name "unconnected-(REG_5V-SS{slash}TR-Pad6)") (class "Default")
      (node (ref "REG_5V") (pin "6") (pinfunction "SS/TR_6") (pintype "bidirectional"))
    )
    (net (code "67") (name "unconnected-(SW1-S-PadC)") (class "Default")
      (node (ref "SW1") (pin "C") (pinfunction "S_C") (pintype "passive"))
    )
  )
)
